# Pyun2Controler2.net
KiCad netlist of a schematic drawn in EAGLE
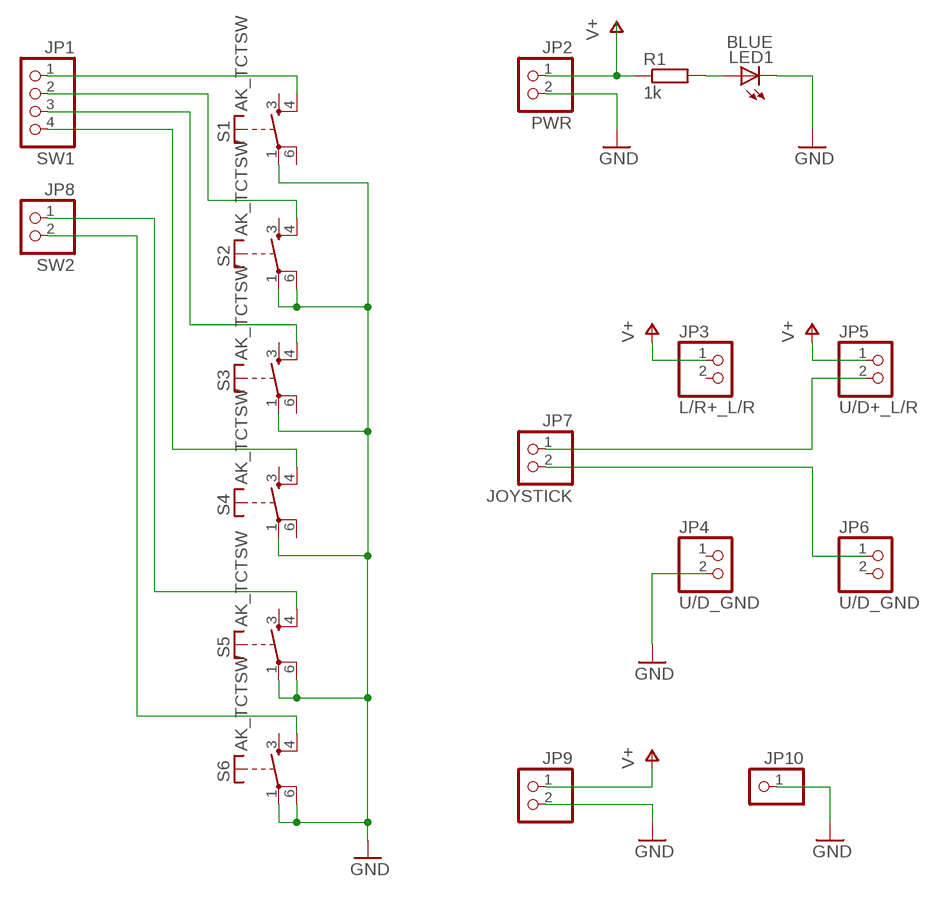
[diagram p0: schematic, sheet 1]

(export (version "E")
  (design (tool "Eeschema 10.0.6"))
  (components
    (comp (ref "JP1")
      (value "SW1")
      (footprint "eagle-import:1X04_90")
      (libsource (lib "eagle-import") (part "PINHD-1X4/90"))
    )
    (comp (ref "JP2")
      (value "PWR")
      (footprint "eagle-import:1X02_90")
      (libsource (lib "eagle-import") (part "PINHD-1X2/90"))
    )
    (comp (ref "JP3")
      (value "L/R+_L/R")
      (footprint "eagle-import:1X02")
      (libsource (lib "eagle-import") (part "PINHD-1X2"))
    )
    (comp (ref "JP4")
      (value "U/D_GND")
      (footprint "eagle-import:1X02")
      (libsource (lib "eagle-import") (part "PINHD-1X2"))
    )
    (comp (ref "JP5")
      (value "U/D+_L/R")
      (footprint "eagle-import:1X02")
      (libsource (lib "eagle-import") (part "PINHD-1X2"))
    )
    (comp (ref "JP6")
      (value "U/D_GND")
      (footprint "eagle-import:1X02")
      (libsource (lib "eagle-import") (part "PINHD-1X2"))
    )
    (comp (ref "JP7")
      (value "JOYSTICK")
      (footprint "eagle-import:1X02_90")
      (libsource (lib "eagle-import") (part "PINHD-1X2/90"))
    )
    (comp (ref "JP8")
      (value "SW2")
      (footprint "eagle-import:1X02_90")
      (libsource (lib "eagle-import") (part "PINHD-1X2/90"))
    )
    (comp (ref "JP9")
      (value "PINHD-1X2/90")
      (footprint "eagle-import:1X02_90")
      (libsource (lib "eagle-import") (part "PINHD-1X2/90"))
    )
    (comp (ref "JP10")
      (value "PINHD-1X1")
      (footprint "eagle-import:1X01")
      (libsource (lib "eagle-import") (part "PINHD-1X1"))
    )
    (comp (ref "LED1")
      (value "BLUE")
      (footprint "eagle-import:LED3MM")
      (libsource (lib "eagle-import") (part "LED3MM"))
    )
    (comp (ref "R1")
      (value "1k")
      (footprint "eagle-import:0207_7")
      (libsource (lib "eagle-import") (part "R-EU_0207/7"))
    )
    (comp (ref "S1")
      (value "AK_TCTSW")
      (footprint "eagle-import:TME1")
      (libsource (lib "eagle-import") (part "AK_TCTSW"))
    )
    (comp (ref "S2")
      (value "AK_TCTSW")
      (footprint "eagle-import:TME1")
      (libsource (lib "eagle-import") (part "AK_TCTSW"))
    )
    (comp (ref "S3")
      (value "AK_TCTSW")
      (footprint "eagle-import:TME1")
      (libsource (lib "eagle-import") (part "AK_TCTSW"))
    )
    (comp (ref "S4")
      (value "AK_TCTSW")
      (footprint "eagle-import:TME1")
      (libsource (lib "eagle-import") (part "AK_TCTSW"))
    )
    (comp (ref "S5")
      (value "AK_TCTSW")
      (footprint "eagle-import:TME1")
      (libsource (lib "eagle-import") (part "AK_TCTSW"))
    )
    (comp (ref "S6")
      (value "AK_TCTSW")
      (footprint "eagle-import:TME1")
      (libsource (lib "eagle-import") (part "AK_TCTSW"))
    )
  )
  (nets
    (net (code "1") (name "GND") (class "Default")
      (node (ref "JP10") (pin "1") (pinfunction "1_1") (pintype "passive"))
      (node (ref "JP2") (pin "2") (pinfunction "2_2") (pintype "passive"))
      (node (ref "JP4") (pin "2") (pinfunction "2_2") (pintype "passive"))
      (node (ref "JP9") (pin "2") (pinfunction "2_2") (pintype "passive"))
      (node (ref "LED1") (pin "K") (pinfunction "C_K") (pintype "passive"))
      (node (ref "S1") (pin "1") (pinfunction "P_1") (pintype "passive"))
      (node (ref "S2") (pin "1") (pinfunction "P_1") (pintype "passive"))
      (node (ref "S2") (pin "6") (pinfunction "P_6") (pintype "passive"))
      (node (ref "S3") (pin "1") (pinfunction "P_1") (pintype "passive"))
      (node (ref "S4") (pin "1") (pinfunction "P_1") (pintype "passive"))
      (node (ref "S5") (pin "1") (pinfunction "P_1") (pintype "passive"))
      (node (ref "S5") (pin "6") (pinfunction "P_6") (pintype "passive"))
      (node (ref "S6") (pin "1") (pinfunction "P_1") (pintype "passive"))
      (node (ref "S6") (pin "6") (pinfunction "P_6") (pintype "passive"))
    )
    (net (code "2") (name "Net-(JP1-Pad1)") (class "Default")
      (node (ref "JP1") (pin "1") (pinfunction "1_1") (pintype "passive"))
      (node (ref "S1") (pin "4") (pinfunction "S_4") (pintype "passive"))
    )
    (net (code "3") (name "Net-(JP1-Pad2)") (class "Default")
      (node (ref "JP1") (pin "2") (pinfunction "2_2") (pintype "passive"))
      (node (ref "S2") (pin "4") (pinfunction "S_4") (pintype "passive"))
    )
    (net (code "4") (name "Net-(JP1-Pad3)") (class "Default")
      (node (ref "JP1") (pin "3") (pinfunction "3_3") (pintype "passive"))
      (node (ref "S3") (pin "4") (pinfunction "S_4") (pintype "passive"))
    )
    (net (code "5") (name "Net-(JP1-Pad4)") (class "Default")
      (node (ref "JP1") (pin "4") (pinfunction "4_4") (pintype "passive"))
      (node (ref "S4") (pin "4") (pinfunction "S_4") (pintype "passive"))
    )
    (net (code "6") (name "Net-(JP5-Pad2)") (class "Default")
      (node (ref "JP5") (pin "2") (pinfunction "2_2") (pintype "passive"))
      (node (ref "JP7") (pin "1") (pinfunction "1_1") (pintype "passive"))
    )
    (net (code "7") (name "Net-(JP6-Pad1)") (class "Default")
      (node (ref "JP6") (pin "1") (pinfunction "1_1") (pintype "passive"))
      (node (ref "JP7") (pin "2") (pinfunction "2_2") (pintype "passive"))
    )
    (net (code "8") (name "Net-(JP8-Pad1)") (class "Default")
      (node (ref "JP8") (pin "1") (pinfunction "1_1") (pintype "passive"))
      (node (ref "S5") (pin "4") (pinfunction "S_4") (pintype "passive"))
    )
    (net (code "9") (name "Net-(JP8-Pad2)") (class "Default")
      (node (ref "JP8") (pin "2") (pinfunction "2_2") (pintype "passive"))
      (node (ref "S6") (pin "4") (pinfunction "S_4") (pintype "passive"))
    )
    (net (code "10") (name "Net-(LED1-PadA)") (class "Default")
      (node (ref "LED1") (pin "A") (pinfunction "A_A") (pintype "passive"))
      (node (ref "R1") (pin "2") (pinfunction "2_2") (pintype "passive"))
    )
    (net (code "11") (name "V+") (class "Default")
      (node (ref "JP2") (pin "1") (pinfunction "1_1") (pintype "passive"))
      (node (ref "JP3") (pin "1") (pinfunction "1_1") (pintype "passive"))
      (node (ref "JP5") (pin "1") (pinfunction "1_1") (pintype "passive"))
      (node (ref "JP9") (pin "1") (pinfunction "1_1") (pintype "passive"))
      (node (ref "R1") (pin "1") (pinfunction "1_1") (pintype "passive"))
    )
    (net (code "12") (name "unconnected-(JP3-Pad2)") (class "Default")
      (node (ref "JP3") (pin "2") (pinfunction "2_2") (pintype "passive"))
    )
    (net (code "13") (name "unconnected-(JP4-Pad1)") (class "Default")
      (node (ref "JP4") (pin "1") (pinfunction "1_1") (pintype "passive"))
    )
    (net (code "14") (name "unconnected-(JP6-Pad2)") (class "Default")
      (node (ref "JP6") (pin "2") (pinfunction "2_2") (pintype "passive"))
    )
    (net (code "15") (name "unconnected-(S1-P-Pad6)") (class "Default")
      (node (ref "S1") (pin "6") (pinfunction "P_6") (pintype "passive"))
    )
    (net (code "16") (name "unconnected-(S1-S-Pad3)") (class "Default")
      (node (ref "S1") (pin "3") (pinfunction "S_3") (pintype "passive"))
    )
    (net (code "17") (name "unconnected-(S2-S-Pad3)") (class "Default")
      (node (ref "S2") (pin "3") (pinfunction "S_3") (pintype "passive"))
    )
    (net (code "18") (name "unconnected-(S3-P-Pad6)") (class "Default")
      (node (ref "S3") (pin "6") (pinfunction "P_6") (pintype "passive"))
    )
    (net (code "19") (name "unconnected-(S3-S-Pad3)") (class "Default")
      (node (ref "S3") (pin "3") (pinfunction "S_3") (pintype "passive"))
    )
    (net (code "20") (name "unconnected-(S4-P-Pad6)") (class "Default")
      (node (ref "S4") (pin "6") (pinfunction "P_6") (pintype "passive"))
    )
    (net (code "21") (name "unconnected-(S4-S-Pad3)") (class "Default")
      (node (ref "S4") (pin "3") (pinfunction "S_3") (pintype "passive"))
    )
    (net (code "22") (name "unconnected-(S5-S-Pad3)") (class "Default")
      (node (ref "S5") (pin "3") (pinfunction "S_3") (pintype "passive"))
    )
    (net (code "23") (name "unconnected-(S6-S-Pad3)") (class "Default")
      (node (ref "S6") (pin "3") (pinfunction "S_3") (pintype "passive"))
    )
  )
)
